# IMU_CAN_Speed_Converter_Board_rev3.net
KiCad netlist of a schematic drawn in EAGLE
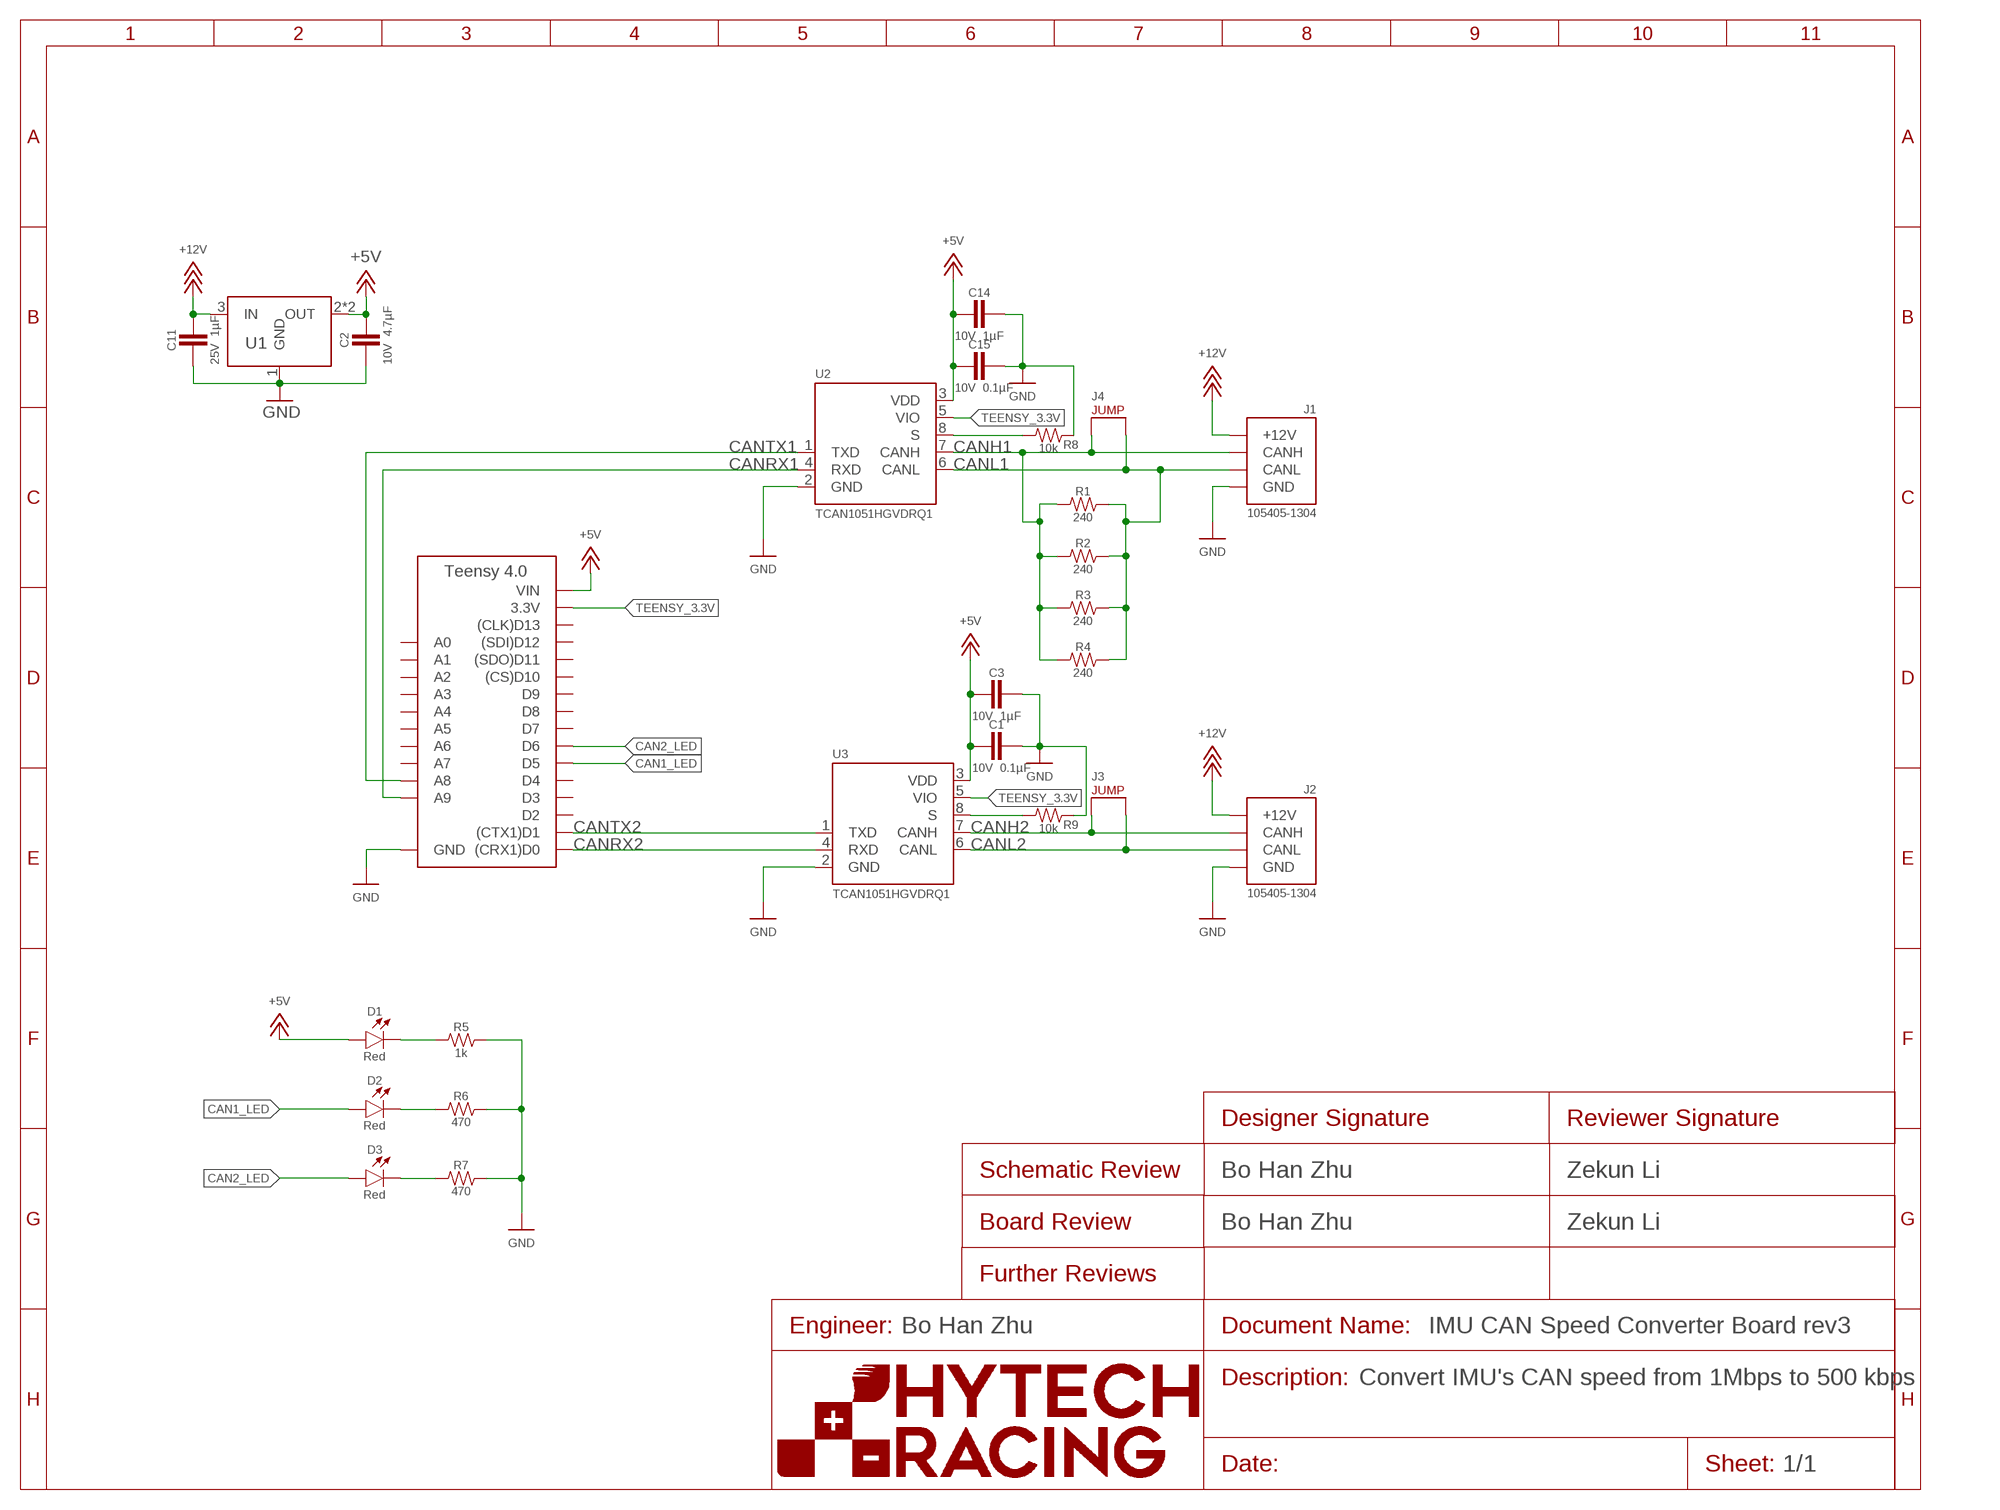
[diagram p0: schematic, sheet 1]

(export (version "E")
  (design (tool "Eeschema 10.0.6"))
  (components
    (comp (ref "A1")
      (value "TEENSY_4.0")
      (footprint "eagle-import:TEENSY_SHORT")
      (libsource (lib "eagle-import") (part "TEENSY_4.0"))
    )
    (comp (ref "C1")
      (value "CAPACITOR_0603_10V_0.1UF")
      (footprint "eagle-import:0603-CAP")
      (fields
        (field (name "CAPACITANCE") "0.1µF")
        (field (name "MANUFACTURER") "Vishay Vitramon")
        (field (name "MPN") "VJ0603Y104JXQPW1BC")
        (field (name "TOLERANCE") "5%")
        (field (name "VOLTAGE") "10V")
      )
      (libsource (lib "eagle-import") (part "CAPACITOR_?_060310V_0.1UF"))
    )
    (comp (ref "C2")
      (value "CAPACITOR_0603_10V_4.7UF")
      (footprint "eagle-import:0603-CAP")
      (fields
        (field (name "CAPACITANCE") "4.7µF")
        (field (name "MANUFACTURER") "Samsung Electro-Mechanics")
        (field (name "MPN") "CL10A475KP8NNNC")
        (field (name "TOLERANCE") "10%")
        (field (name "VOLTAGE") "10V")
      )
      (libsource (lib "eagle-import") (part "CAPACITOR_?_060310V_4.7UF"))
    )
    (comp (ref "C3")
      (value "CAPACITOR_0603_10V_1UF")
      (footprint "eagle-import:0603-CAP")
      (fields
        (field (name "CAPACITANCE") "1µF")
        (field (name "MANUFACTURER") "Yageo")
        (field (name "MPN") "CC0603KRX7R6BB105")
        (field (name "TOLERANCE") "10%")
        (field (name "VOLTAGE") "10V")
      )
      (libsource (lib "eagle-import") (part "CAPACITOR_?_060310V_1UF"))
    )
    (comp (ref "C11")
      (value "CAPACITOR_0603_25V_1UF")
      (footprint "eagle-import:0603-CAP")
      (fields
        (field (name "CAPACITANCE") "1µF")
        (field (name "MANUFACTURER") "Samsung Electro-Mechanics")
        (field (name "MPN") "CL10B105KA8NNNC")
        (field (name "TOLERANCE") "10%")
        (field (name "VOLTAGE") "25V")
      )
      (libsource (lib "eagle-import") (part "CAPACITOR_?_060325V_1UF"))
    )
    (comp (ref "C14")
      (value "CAPACITOR_0603_10V_1UF")
      (footprint "eagle-import:0603-CAP")
      (fields
        (field (name "CAPACITANCE") "1µF")
        (field (name "MANUFACTURER") "Yageo")
        (field (name "MPN") "CC0603KRX7R6BB105")
        (field (name "TOLERANCE") "10%")
        (field (name "VOLTAGE") "10V")
      )
      (libsource (lib "eagle-import") (part "CAPACITOR_?_060310V_1UF"))
    )
    (comp (ref "C15")
      (value "CAPACITOR_0603_10V_0.1UF")
      (footprint "eagle-import:0603-CAP")
      (fields
        (field (name "CAPACITANCE") "0.1µF")
        (field (name "MANUFACTURER") "Vishay Vitramon")
        (field (name "MPN") "VJ0603Y104JXQPW1BC")
        (field (name "TOLERANCE") "5%")
        (field (name "VOLTAGE") "10V")
      )
      (libsource (lib "eagle-import") (part "CAPACITOR_?_060310V_0.1UF"))
    )
    (comp (ref "D1")
      (value "LED_0603_RED")
      (footprint "eagle-import:0603-LED")
      (fields
        (field (name "COLOR") "Red")
        (field (name "MANUFACTURER") "Kingbright")
        (field (name "MPN") "APT1608SECK/J3-PRV")
      )
      (libsource (lib "eagle-import") (part "LED_?_0603RED"))
    )
    (comp (ref "D2")
      (value "LED_0603_RED")
      (footprint "eagle-import:0603-LED")
      (fields
        (field (name "COLOR") "Red")
        (field (name "MANUFACTURER") "Kingbright")
        (field (name "MPN") "APT1608SECK/J3-PRV")
      )
      (libsource (lib "eagle-import") (part "LED_?_0603RED"))
    )
    (comp (ref "D3")
      (value "LED_0603_RED")
      (footprint "eagle-import:0603-LED")
      (fields
        (field (name "COLOR") "Red")
        (field (name "MANUFACTURER") "Kingbright")
        (field (name "MPN") "APT1608SECK/J3-PRV")
      )
      (libsource (lib "eagle-import") (part "LED_?_0603RED"))
    )
    (comp (ref "J1")
      (value "CONNECTOR-CAN_NF_S_RA_BLACK")
      (footprint "eagle-import:MOLEX_NANOFIT_SMD_RIGHTANGLE_04")
      (fields (field (name "MANUFACTURER") "Molex") (field (name "MPN") "105405-1304"))
      (libsource (lib "eagle-import") (part "CONNECTOR-CAN_?_NF_S_RABLACK"))
    )
    (comp (ref "J2")
      (value "CONNECTOR-CAN_NF_S_RA_BLACK")
      (footprint "eagle-import:MOLEX_NANOFIT_SMD_RIGHTANGLE_04")
      (fields (field (name "MANUFACTURER") "Molex") (field (name "MPN") "105405-1304"))
      (libsource (lib "eagle-import") (part "CONNECTOR-CAN_?_NF_S_RABLACK"))
    )
    (comp (ref "J3")
      (value "JUMPER_1X02_")
      (footprint "eagle-import:1X02")
      (libsource (lib "eagle-import") (part "JUMPER_?_1X02"))
    )
    (comp (ref "J4")
      (value "JUMPER_1X02_")
      (footprint "eagle-import:1X02")
      (libsource (lib "eagle-import") (part "JUMPER_?_1X02"))
    )
    (comp (ref "R1")
      (value "RESISTOR_0603_240")
      (footprint "eagle-import:0603-RES")
      (fields
        (field (name "MANUFACTURER") "Yageo")
        (field (name "MPN") "RC0603FR-07240RL")
        (field (name "POWER") "0.1W")
        (field (name "RESISTANCE") "240")
      )
      (libsource (lib "eagle-import") (part "RESISTOR_?_0603240"))
    )
    (comp (ref "R2")
      (value "RESISTOR_0603_240")
      (footprint "eagle-import:0603-RES")
      (fields
        (field (name "MANUFACTURER") "Yageo")
        (field (name "MPN") "RC0603FR-07240RL")
        (field (name "POWER") "0.1W")
        (field (name "RESISTANCE") "240")
      )
      (libsource (lib "eagle-import") (part "RESISTOR_?_0603240"))
    )
    (comp (ref "R3")
      (value "RESISTOR_0603_240")
      (footprint "eagle-import:0603-RES")
      (fields
        (field (name "MANUFACTURER") "Yageo")
        (field (name "MPN") "RC0603FR-07240RL")
        (field (name "POWER") "0.1W")
        (field (name "RESISTANCE") "240")
      )
      (libsource (lib "eagle-import") (part "RESISTOR_?_0603240"))
    )
    (comp (ref "R4")
      (value "RESISTOR_0603_240")
      (footprint "eagle-import:0603-RES")
      (fields
        (field (name "MANUFACTURER") "Yageo")
        (field (name "MPN") "RC0603FR-07240RL")
        (field (name "POWER") "0.1W")
        (field (name "RESISTANCE") "240")
      )
      (libsource (lib "eagle-import") (part "RESISTOR_?_0603240"))
    )
    (comp (ref "R5")
      (value "RESISTOR_0603_1K")
      (footprint "eagle-import:0603-RES")
      (fields
        (field (name "MANUFACTURER") "Yageo")
        (field (name "MPN") "RC0603FR-071KL")
        (field (name "POWER") "0.1W")
        (field (name "RESISTANCE") "1k")
      )
      (libsource (lib "eagle-import") (part "RESISTOR_?_06031K"))
    )
    (comp (ref "R6")
      (value "RESISTOR_0603_470")
      (footprint "eagle-import:0603-RES")
      (fields
        (field (name "MANUFACTURER") "Panasonic Electronic Components")
        (field (name "MPN") "ERJ-PA3F4700V")
        (field (name "POWER") "0.25W")
        (field (name "RESISTANCE") "470")
      )
      (libsource (lib "eagle-import") (part "RESISTOR_?_0603470"))
    )
    (comp (ref "R7")
      (value "RESISTOR_0603_470")
      (footprint "eagle-import:0603-RES")
      (fields
        (field (name "MANUFACTURER") "Panasonic Electronic Components")
        (field (name "MPN") "ERJ-PA3F4700V")
        (field (name "POWER") "0.25W")
        (field (name "RESISTANCE") "470")
      )
      (libsource (lib "eagle-import") (part "RESISTOR_?_0603470"))
    )
    (comp (ref "R8")
      (value "RESISTOR_0603_10K")
      (footprint "eagle-import:0603-RES")
      (fields
        (field (name "MANUFACTURER") "Yageo")
        (field (name "MPN") "RC0603FR-0710KL")
        (field (name "POWER") "0.1W")
        (field (name "RESISTANCE") "10k")
      )
      (libsource (lib "eagle-import") (part "RESISTOR_?_060310K"))
    )
    (comp (ref "R9")
      (value "RESISTOR_0603_10K")
      (footprint "eagle-import:0603-RES")
      (fields
        (field (name "MANUFACTURER") "Yageo")
        (field (name "MPN") "RC0603FR-0710KL")
        (field (name "POWER") "0.1W")
        (field (name "RESISTANCE") "10k")
      )
      (libsource (lib "eagle-import") (part "RESISTOR_?_060310K"))
    )
    (comp (ref "U1")
      (value "VOLTAGE_REGULATOR_SOT223_5V")
      (footprint "eagle-import:SOT223")
      (fields (field (name "MANUFACTURER") "STMicroelectronics") (field (name "MPN") "LDL1117S50R"))
      (libsource (lib "eagle-import") (part "VOLTAGE_REGULATOR_?_SOT2235V"))
    )
    (comp (ref "U2")
      (value "TCAN1051HQV-Q1")
      (footprint "eagle-import:SOIC-08(NARROW,0.15_)")
      (fields (field (name "MANUFACTURER") "Texas Instruments") (field (name "MPN") "TCAN1051HGVDRQ1"))
      (libsource (lib "eagle-import") (part "TCAN1051V-Q1HQ"))
    )
    (comp (ref "U3")
      (value "TCAN1051HQV-Q1")
      (footprint "eagle-import:SOIC-08(NARROW,0.15_)")
      (fields (field (name "MANUFACTURER") "Texas Instruments") (field (name "MPN") "TCAN1051HGVDRQ1"))
      (libsource (lib "eagle-import") (part "TCAN1051V-Q1HQ"))
    )
  )
  (nets
    (net (code "1") (name "+5V") (class "Default")
      (node (ref "A1") (pin "VIN") (pinfunction "VIN_VIN") (pintype "power_in"))
      (node (ref "C1") (pin "2") (pinfunction "2_2") (pintype "passive"))
      (node (ref "C14") (pin "2") (pinfunction "2_2") (pintype "passive"))
      (node (ref "C15") (pin "2") (pinfunction "2_2") (pintype "passive"))
      (node (ref "C2") (pin "1") (pinfunction "1_1") (pintype "passive"))
      (node (ref "C3") (pin "2") (pinfunction "2_2") (pintype "passive"))
      (node (ref "D1") (pin "2") (pinfunction "A_2") (pintype "passive"))
      (node (ref "U1") (pin "2") (pinfunction "OUT_2") (pintype "power_in"))
      (node (ref "U1") (pin "4") (pinfunction "OUT_4") (pintype "power_in"))
      (node (ref "U2") (pin "3") (pinfunction "VDD_3") (pintype "power_in"))
      (node (ref "U3") (pin "3") (pinfunction "VDD_3") (pintype "power_in"))
    )
    (net (code "2") (name "+12V") (class "Default")
      (node (ref "C11") (pin "1") (pinfunction "1_1") (pintype "passive"))
      (node (ref "J1") (pin "1") (pinfunction "+12V_1") (pintype "power_in"))
      (node (ref "J2") (pin "1") (pinfunction "+12V_1") (pintype "power_in"))
      (node (ref "U1") (pin "3") (pinfunction "IN_3") (pintype "power_in"))
    )
    (net (code "3") (name "/CANH1") (class "Default")
      (node (ref "J1") (pin "4") (pinfunction "CANH_4") (pintype "bidirectional"))
      (node (ref "J4") (pin "1") (pinfunction "P$1_1") (pintype "passive"))
      (node (ref "R1") (pin "1") (pinfunction "1_1") (pintype "passive"))
      (node (ref "R2") (pin "1") (pinfunction "1_1") (pintype "passive"))
      (node (ref "R3") (pin "1") (pinfunction "1_1") (pintype "passive"))
      (node (ref "R4") (pin "1") (pinfunction "1_1") (pintype "passive"))
      (node (ref "U2") (pin "7") (pinfunction "CANH_7") (pintype "output"))
    )
    (net (code "4") (name "/CANH2") (class "Default")
      (node (ref "J2") (pin "4") (pinfunction "CANH_4") (pintype "bidirectional"))
      (node (ref "J3") (pin "1") (pinfunction "P$1_1") (pintype "passive"))
      (node (ref "U3") (pin "7") (pinfunction "CANH_7") (pintype "output"))
    )
    (net (code "5") (name "/CANL1") (class "Default")
      (node (ref "J1") (pin "3") (pinfunction "CANL_3") (pintype "bidirectional"))
      (node (ref "J4") (pin "2") (pinfunction "P$2_2") (pintype "passive"))
      (node (ref "R1") (pin "2") (pinfunction "2_2") (pintype "passive"))
      (node (ref "R2") (pin "2") (pinfunction "2_2") (pintype "passive"))
      (node (ref "R3") (pin "2") (pinfunction "2_2") (pintype "passive"))
      (node (ref "R4") (pin "2") (pinfunction "2_2") (pintype "passive"))
      (node (ref "U2") (pin "6") (pinfunction "CANL_6") (pintype "bidirectional"))
    )
    (net (code "6") (name "/CANL2") (class "Default")
      (node (ref "J2") (pin "3") (pinfunction "CANL_3") (pintype "bidirectional"))
      (node (ref "J3") (pin "2") (pinfunction "P$2_2") (pintype "passive"))
      (node (ref "U3") (pin "6") (pinfunction "CANL_6") (pintype "bidirectional"))
    )
    (net (code "7") (name "/CANRX1") (class "Default")
      (node (ref "A1") (pin "D23") (pinfunction "A9_D23") (pintype "bidirectional"))
      (node (ref "U2") (pin "4") (pinfunction "RXD_4") (pintype "output"))
    )
    (net (code "8") (name "/CANRX2") (class "Default")
      (node (ref "A1") (pin "D0") (pinfunction "(CRX1)D0_D0") (pintype "bidirectional"))
      (node (ref "U3") (pin "4") (pinfunction "RXD_4") (pintype "output"))
    )
    (net (code "9") (name "/CANTX1") (class "Default")
      (node (ref "A1") (pin "D22") (pinfunction "A8_D22") (pintype "bidirectional"))
      (node (ref "U2") (pin "1") (pinfunction "TXD_1") (pintype "input"))
    )
    (net (code "10") (name "/CANTX2") (class "Default")
      (node (ref "A1") (pin "D1") (pinfunction "(CTX1)D1_D1") (pintype "bidirectional"))
      (node (ref "U3") (pin "1") (pinfunction "TXD_1") (pintype "input"))
    )
    (net (code "11") (name "CAN1_LED") (class "Default")
      (node (ref "A1") (pin "D5") (pinfunction "D5_D5") (pintype "bidirectional"))
      (node (ref "D2") (pin "2") (pinfunction "A_2") (pintype "passive"))
    )
    (net (code "12") (name "CAN2_LED") (class "Default")
      (node (ref "A1") (pin "D6") (pinfunction "D6_D6") (pintype "bidirectional"))
      (node (ref "D3") (pin "2") (pinfunction "A_2") (pintype "passive"))
    )
    (net (code "13") (name "GND") (class "Default")
      (node (ref "A1") (pin "AGND/GND") (pinfunction "GND_AGND/GND") (pintype "power_in"))
      (node (ref "A1") (pin "GND") (pinfunction "GND_GND") (pintype "power_in"))
      (node (ref "C1") (pin "1") (pinfunction "1_1") (pintype "passive"))
      (node (ref "C11") (pin "2") (pinfunction "2_2") (pintype "passive"))
      (node (ref "C14") (pin "1") (pinfunction "1_1") (pintype "passive"))
      (node (ref "C15") (pin "1") (pinfunction "1_1") (pintype "passive"))
      (node (ref "C2") (pin "2") (pinfunction "2_2") (pintype "passive"))
      (node (ref "C3") (pin "1") (pinfunction "1_1") (pintype "passive"))
      (node (ref "J1") (pin "2") (pinfunction "GND_2") (pintype "power_in"))
      (node (ref "J2") (pin "2") (pinfunction "GND_2") (pintype "power_in"))
      (node (ref "R5") (pin "2") (pinfunction "2_2") (pintype "passive"))
      (node (ref "R6") (pin "2") (pinfunction "2_2") (pintype "passive"))
      (node (ref "R7") (pin "2") (pinfunction "2_2") (pintype "passive"))
      (node (ref "R8") (pin "2") (pinfunction "2_2") (pintype "passive"))
      (node (ref "R9") (pin "2") (pinfunction "2_2") (pintype "passive"))
      (node (ref "U1") (pin "1") (pinfunction "GND_1") (pintype "power_in"))
      (node (ref "U2") (pin "2") (pinfunction "GND_2") (pintype "power_in"))
      (node (ref "U3") (pin "2") (pinfunction "GND_2") (pintype "power_in"))
    )
    (net (code "14") (name "Net-(D1-C)") (class "Default")
      (node (ref "D1") (pin "1") (pinfunction "C_1") (pintype "passive"))
      (node (ref "R5") (pin "1") (pinfunction "1_1") (pintype "passive"))
    )
    (net (code "15") (name "Net-(D2-C)") (class "Default")
      (node (ref "D2") (pin "1") (pinfunction "C_1") (pintype "passive"))
      (node (ref "R6") (pin "1") (pinfunction "1_1") (pintype "passive"))
    )
    (net (code "16") (name "Net-(D3-C)") (class "Default")
      (node (ref "D3") (pin "1") (pinfunction "C_1") (pintype "passive"))
      (node (ref "R7") (pin "1") (pinfunction "1_1") (pintype "passive"))
    )
    (net (code "17") (name "Net-(U2-S)") (class "Default")
      (node (ref "R8") (pin "1") (pinfunction "1_1") (pintype "passive"))
      (node (ref "U2") (pin "8") (pinfunction "S_8") (pintype "input"))
    )
    (net (code "18") (name "Net-(U3-S)") (class "Default")
      (node (ref "R9") (pin "1") (pinfunction "1_1") (pintype "passive"))
      (node (ref "U3") (pin "8") (pinfunction "S_8") (pintype "input"))
    )
    (net (code "19") (name "TEENSY_3.3V") (class "Default")
      (node (ref "A1") (pin "3.3V") (pinfunction "3.3V_3.3V") (pintype "power_in"))
      (node (ref "U2") (pin "5") (pinfunction "VIO_5") (pintype "power_in"))
      (node (ref "U3") (pin "5") (pinfunction "VIO_5") (pintype "power_in"))
    )
    (net (code "20") (name "unconnected-(A1-(CLK)D13-PadD13)") (class "Default")
      (node (ref "A1") (pin "D13") (pinfunction "(CLK)D13_D13") (pintype "bidirectional"))
    )
    (net (code "21") (name "unconnected-(A1-(CS)D10-PadD10)") (class "Default")
      (node (ref "A1") (pin "D10") (pinfunction "(CS)D10_D10") (pintype "bidirectional"))
    )
    (net (code "22") (name "unconnected-(A1-(SDI)D12-PadD12)") (class "Default")
      (node (ref "A1") (pin "D12") (pinfunction "(SDI)D12_D12") (pintype "bidirectional"))
    )
    (net (code "23") (name "unconnected-(A1-(SDO)D11-PadD11)") (class "Default")
      (node (ref "A1") (pin "D11") (pinfunction "(SDO)D11_D11") (pintype "bidirectional"))
    )
    (net (code "24") (name "unconnected-(A1-A0-PadD14)") (class "Default")
      (node (ref "A1") (pin "D14") (pinfunction "A0_D14") (pintype "bidirectional"))
    )
    (net (code "25") (name "unconnected-(A1-A1-PadD15)") (class "Default")
      (node (ref "A1") (pin "D15") (pinfunction "A1_D15") (pintype "bidirectional"))
    )
    (net (code "26") (name "unconnected-(A1-A2-PadD16)") (class "Default")
      (node (ref "A1") (pin "D16") (pinfunction "A2_D16") (pintype "bidirectional"))
    )
    (net (code "27") (name "unconnected-(A1-A3-PadD17)") (class "Default")
      (node (ref "A1") (pin "D17") (pinfunction "A3_D17") (pintype "bidirectional"))
    )
    (net (code "28") (name "unconnected-(A1-A4-PadD18)") (class "Default")
      (node (ref "A1") (pin "D18") (pinfunction "A4_D18") (pintype "bidirectional"))
    )
    (net (code "29") (name "unconnected-(A1-A5-PadD19)") (class "Default")
      (node (ref "A1") (pin "D19") (pinfunction "A5_D19") (pintype "bidirectional"))
    )
    (net (code "30") (name "unconnected-(A1-A6-PadD20)") (class "Default")
      (node (ref "A1") (pin "D20") (pinfunction "A6_D20") (pintype "bidirectional"))
    )
    (net (code "31") (name "unconnected-(A1-A7-PadD21)") (class "Default")
      (node (ref "A1") (pin "D21") (pinfunction "A7_D21") (pintype "bidirectional"))
    )
    (net (code "32") (name "unconnected-(A1-PadD2)") (class "Default")
      (node (ref "A1") (pin "D2") (pinfunction "D2_D2") (pintype "bidirectional"))
    )
    (net (code "33") (name "unconnected-(A1-PadD3)") (class "Default")
      (node (ref "A1") (pin "D3") (pinfunction "D3_D3") (pintype "bidirectional"))
    )
    (net (code "34") (name "unconnected-(A1-PadD4)") (class "Default")
      (node (ref "A1") (pin "D4") (pinfunction "D4_D4") (pintype "bidirectional"))
    )
    (net (code "35") (name "unconnected-(A1-PadD7)") (class "Default")
      (node (ref "A1") (pin "D7") (pinfunction "D7_D7") (pintype "bidirectional"))
    )
    (net (code "36") (name "unconnected-(A1-PadD8)") (class "Default")
      (node (ref "A1") (pin "D8") (pinfunction "D8_D8") (pintype "bidirectional"))
    )
    (net (code "37") (name "unconnected-(A1-PadD9)") (class "Default")
      (node (ref "A1") (pin "D9") (pinfunction "D9_D9") (pintype "bidirectional"))
    )
  )
)
